# Double_Socket.net
KiCad netlist of a schematic drawn in EAGLE
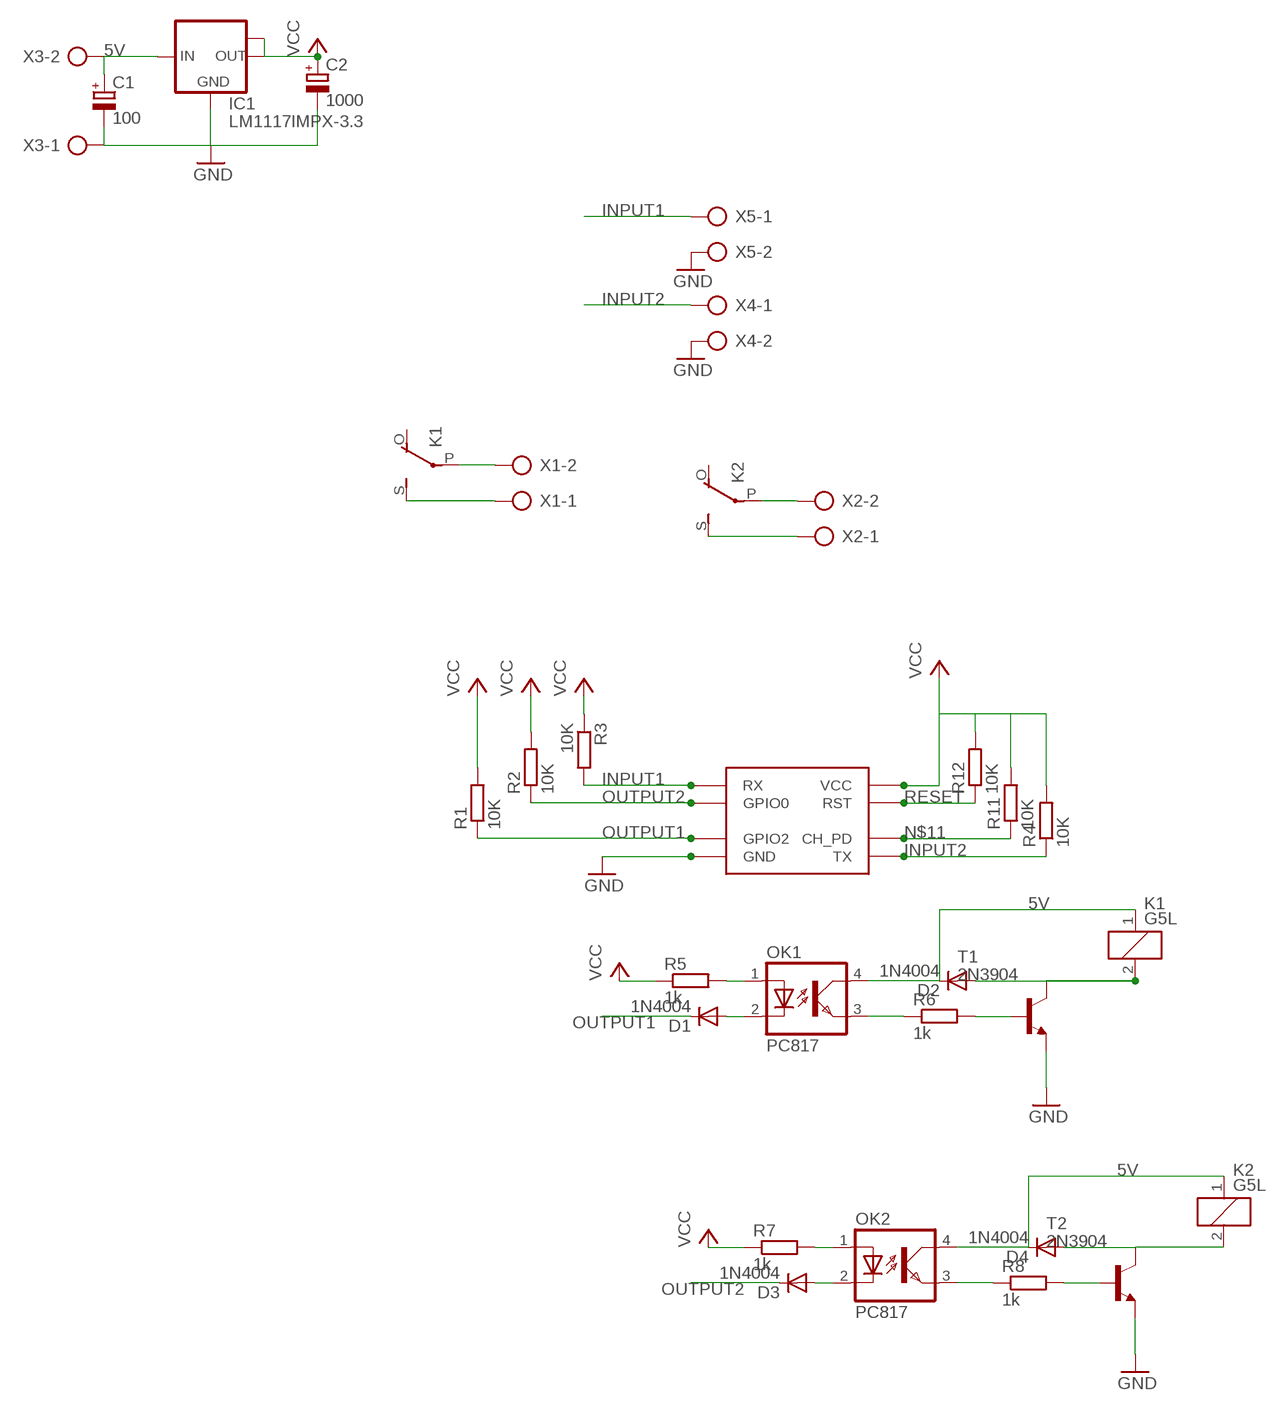
[diagram p0: schematic, sheet 1]

(export (version "E")
  (design (tool "Eeschema 10.0.6"))
  (components
    (comp (ref "C1")
      (value "100")
      (footprint "eagle-import:E5-10,5")
      (libsource (lib "eagle-import") (part "CPOL-EUE5-10.5"))
    )
    (comp (ref "C2")
      (value "1000")
      (footprint "eagle-import:E5-10,5")
      (libsource (lib "eagle-import") (part "CPOL-EUE5-10.5"))
    )
    (comp (ref "D1")
      (value "1N4004")
      (footprint "eagle-import:DO41-10")
      (libsource (lib "eagle-import") (part "1N4004"))
    )
    (comp (ref "D2")
      (value "1N4004")
      (footprint "eagle-import:DO41-10")
      (libsource (lib "eagle-import") (part "1N4004"))
    )
    (comp (ref "D3")
      (value "1N4004")
      (footprint "eagle-import:DO41-10")
      (libsource (lib "eagle-import") (part "1N4004"))
    )
    (comp (ref "D4")
      (value "1N4004")
      (footprint "eagle-import:DO41-10")
      (libsource (lib "eagle-import") (part "1N4004"))
    )
    (comp (ref "IC1")
      (value "LM1117IMPX-3.3")
      (footprint "eagle-import:SOT223")
      (libsource (lib "eagle-import") (part "LM1117IMPX-3.3"))
    )
    (comp (ref "K1")
      (value "G5L")
      (footprint "eagle-import:G5LE")
      (libsource (lib "eagle-import") (part "G5L"))
    )
    (comp (ref "K2")
      (value "G5L")
      (footprint "eagle-import:G5LE")
      (libsource (lib "eagle-import") (part "G5L"))
    )
    (comp (ref "OK1")
      (value "PC817")
      (footprint "eagle-import:DIL04")
      (fields (field (name "MPN") "PC817X4J000F"))
      (libsource (lib "eagle-import") (part "PC817"))
    )
    (comp (ref "OK2")
      (value "PC817")
      (footprint "eagle-import:DIL04")
      (fields (field (name "MPN") "PC817X4J000F"))
      (libsource (lib "eagle-import") (part "PC817"))
    )
    (comp (ref "R1")
      (value "10K")
      (footprint "eagle-import:M0805")
      (libsource (lib "eagle-import") (part "R-EU_M0805"))
    )
    (comp (ref "R2")
      (value "10K")
      (footprint "eagle-import:M0805")
      (libsource (lib "eagle-import") (part "R-EU_M0805"))
    )
    (comp (ref "R3")
      (value "10K")
      (footprint "eagle-import:M0805")
      (libsource (lib "eagle-import") (part "R-EU_M0805"))
    )
    (comp (ref "R4")
      (value "10K")
      (footprint "eagle-import:M0805")
      (libsource (lib "eagle-import") (part "R-EU_M0805"))
    )
    (comp (ref "R5")
      (value "1k")
      (footprint "eagle-import:M0805")
      (libsource (lib "eagle-import") (part "R-EU_M0805"))
    )
    (comp (ref "R6")
      (value "1k")
      (footprint "eagle-import:M0805")
      (libsource (lib "eagle-import") (part "R-EU_M0805"))
    )
    (comp (ref "R7")
      (value "1k")
      (footprint "eagle-import:M0805")
      (libsource (lib "eagle-import") (part "R-EU_M0805"))
    )
    (comp (ref "R8")
      (value "1k")
      (footprint "eagle-import:M0805")
      (libsource (lib "eagle-import") (part "R-EU_M0805"))
    )
    (comp (ref "R11")
      (value "10K")
      (footprint "eagle-import:M0805")
      (libsource (lib "eagle-import") (part "R-EU_M0805"))
    )
    (comp (ref "R12")
      (value "10K")
      (footprint "eagle-import:M0805")
      (libsource (lib "eagle-import") (part "R-EU_M0805"))
    )
    (comp (ref "T1")
      (value "2N3904")
      (footprint "eagle-import:TO92")
      (libsource (lib "eagle-import") (part "2N3904"))
    )
    (comp (ref "T2")
      (value "2N3904")
      (footprint "eagle-import:TO92")
      (libsource (lib "eagle-import") (part "2N3904"))
    )
    (comp (ref "U$2")
      (value "ESP8266")
      (footprint "eagle-import:ESP8266")
      (libsource (lib "eagle-import") (part "ESP8266"))
    )
    (comp (ref "X1")
      (value "AK500/2-H")
      (footprint "eagle-import:AK500_2-H")
      (libsource (lib "eagle-import") (part "AK500/2-H"))
    )
    (comp (ref "X2")
      (value "AK500/2-H")
      (footprint "eagle-import:AK500_2-H")
      (libsource (lib "eagle-import") (part "AK500/2-H"))
    )
    (comp (ref "X3")
      (value "AK500/2-H")
      (footprint "eagle-import:AK500_2-H")
      (libsource (lib "eagle-import") (part "AK500/2-H"))
    )
    (comp (ref "X4")
      (value "AK500/2-H")
      (footprint "eagle-import:AK500_2-H")
      (libsource (lib "eagle-import") (part "AK500/2-H"))
    )
    (comp (ref "X5")
      (value "AK500/2-H")
      (footprint "eagle-import:AK500_2-H")
      (libsource (lib "eagle-import") (part "AK500/2-H"))
    )
  )
  (nets
    (net (code "1") (name "/5V") (class "Default")
      (node (ref "C1") (pin "+") (pinfunction "+_+") (pintype "passive"))
      (node (ref "D2") (pin "C") (pinfunction "C_C") (pintype "passive"))
      (node (ref "D4") (pin "C") (pinfunction "C_C") (pintype "passive"))
      (node (ref "IC1") (pin "3") (pinfunction "IN_3") (pintype "input"))
      (node (ref "K1") (pin "1") (pinfunction "1_1") (pintype "passive"))
      (node (ref "K2") (pin "1") (pinfunction "1_1") (pintype "passive"))
      (node (ref "OK1") (pin "4") (pinfunction "COL_4") (pintype "passive"))
      (node (ref "OK2") (pin "4") (pinfunction "COL_4") (pintype "passive"))
      (node (ref "X3") (pin "2") (pinfunction "KL_2") (pintype "passive"))
    )
    (net (code "2") (name "/INPUT1") (class "Default")
      (node (ref "R3") (pin "2") (pinfunction "2_2") (pintype "passive"))
      (node (ref "U$2") (pin "RX") (pinfunction "RX_RX") (pintype "bidirectional"))
      (node (ref "X5") (pin "1") (pinfunction "KL_1") (pintype "passive"))
    )
    (net (code "3") (name "/INPUT2") (class "Default")
      (node (ref "R4") (pin "1") (pinfunction "1_1") (pintype "passive"))
      (node (ref "U$2") (pin "TX") (pinfunction "TX_TX") (pintype "bidirectional"))
      (node (ref "X4") (pin "1") (pinfunction "KL_1") (pintype "passive"))
    )
    (net (code "4") (name "/N$11") (class "Default")
      (node (ref "R11") (pin "1") (pinfunction "1_1") (pintype "passive"))
      (node (ref "U$2") (pin "CH_PD") (pinfunction "CH_PD_CH_PD") (pintype "bidirectional"))
    )
    (net (code "5") (name "/OUTPUT1") (class "Default")
      (node (ref "D1") (pin "C") (pinfunction "C_C") (pintype "passive"))
      (node (ref "R1") (pin "1") (pinfunction "1_1") (pintype "passive"))
      (node (ref "U$2") (pin "GPIO2") (pinfunction "GPIO2_GPIO2") (pintype "bidirectional"))
    )
    (net (code "6") (name "/OUTPUT2") (class "Default")
      (node (ref "D3") (pin "C") (pinfunction "C_C") (pintype "passive"))
      (node (ref "R2") (pin "1") (pinfunction "1_1") (pintype "passive"))
      (node (ref "U$2") (pin "GPIO0") (pinfunction "GPIO0_GPIO0") (pintype "bidirectional"))
    )
    (net (code "7") (name "/RESET") (class "Default")
      (node (ref "R12") (pin "1") (pinfunction "1_1") (pintype "passive"))
      (node (ref "U$2") (pin "RST") (pinfunction "RST_RST") (pintype "bidirectional"))
    )
    (net (code "8") (name "GND") (class "Default")
      (node (ref "C1") (pin "-") (pinfunction "-_-") (pintype "passive"))
      (node (ref "C2") (pin "-") (pinfunction "-_-") (pintype "passive"))
      (node (ref "IC1") (pin "1") (pinfunction "GND_1") (pintype "input"))
      (node (ref "T1") (pin "3") (pinfunction "E_3") (pintype "passive"))
      (node (ref "T2") (pin "3") (pinfunction "E_3") (pintype "passive"))
      (node (ref "U$2") (pin "GND") (pinfunction "GND_GND") (pintype "bidirectional"))
      (node (ref "X3") (pin "1") (pinfunction "KL_1") (pintype "passive"))
      (node (ref "X4") (pin "2") (pinfunction "KL_2") (pintype "passive"))
      (node (ref "X5") (pin "2") (pinfunction "KL_2") (pintype "passive"))
    )
    (net (code "9") (name "Net-(OK1-A)") (class "Default")
      (node (ref "OK1") (pin "1") (pinfunction "A_1") (pintype "passive"))
      (node (ref "R5") (pin "2") (pinfunction "2_2") (pintype "passive"))
    )
    (net (code "10") (name "Net-(OK1-C)") (class "Default")
      (node (ref "D1") (pin "A") (pinfunction "A_A") (pintype "passive"))
      (node (ref "OK1") (pin "2") (pinfunction "C_2") (pintype "passive"))
    )
    (net (code "11") (name "Net-(OK1-EMIT)") (class "Default")
      (node (ref "OK1") (pin "3") (pinfunction "EMIT_3") (pintype "passive"))
      (node (ref "R6") (pin "1") (pinfunction "1_1") (pintype "passive"))
    )
    (net (code "12") (name "Net-(OK2-A)") (class "Default")
      (node (ref "OK2") (pin "1") (pinfunction "A_1") (pintype "passive"))
      (node (ref "R7") (pin "2") (pinfunction "2_2") (pintype "passive"))
    )
    (net (code "13") (name "Net-(OK2-C)") (class "Default")
      (node (ref "D3") (pin "A") (pinfunction "A_A") (pintype "passive"))
      (node (ref "OK2") (pin "2") (pinfunction "C_2") (pintype "passive"))
    )
    (net (code "14") (name "Net-(OK2-EMIT)") (class "Default")
      (node (ref "OK2") (pin "3") (pinfunction "EMIT_3") (pintype "passive"))
      (node (ref "R8") (pin "1") (pinfunction "1_1") (pintype "passive"))
    )
    (net (code "15") (name "Net-(T1-B)") (class "Default")
      (node (ref "R6") (pin "2") (pinfunction "2_2") (pintype "passive"))
      (node (ref "T1") (pin "2") (pinfunction "B_2") (pintype "passive"))
    )
    (net (code "16") (name "Net-(T1-C)") (class "Default")
      (node (ref "D2") (pin "A") (pinfunction "A_A") (pintype "passive"))
      (node (ref "K1") (pin "2") (pinfunction "2_2") (pintype "passive"))
      (node (ref "T1") (pin "1") (pinfunction "C_1") (pintype "passive"))
    )
    (net (code "17") (name "Net-(T2-B)") (class "Default")
      (node (ref "R8") (pin "2") (pinfunction "2_2") (pintype "passive"))
      (node (ref "T2") (pin "2") (pinfunction "B_2") (pintype "passive"))
    )
    (net (code "18") (name "Net-(T2-C)") (class "Default")
      (node (ref "D4") (pin "A") (pinfunction "A_A") (pintype "passive"))
      (node (ref "K2") (pin "2") (pinfunction "2_2") (pintype "passive"))
      (node (ref "T2") (pin "1") (pinfunction "C_1") (pintype "passive"))
    )
    (net (code "19") (name "Net-(X1A-KL)") (class "Default")
      (node (ref "K1") (pin "S") (pinfunction "S_S") (pintype "passive"))
      (node (ref "X1") (pin "1") (pinfunction "KL_1") (pintype "passive"))
    )
    (net (code "20") (name "Net-(X1B-KL)") (class "Default")
      (node (ref "K1") (pin "P") (pinfunction "P_P") (pintype "passive"))
      (node (ref "X1") (pin "2") (pinfunction "KL_2") (pintype "passive"))
    )
    (net (code "21") (name "Net-(X2A-KL)") (class "Default")
      (node (ref "K2") (pin "S") (pinfunction "S_S") (pintype "passive"))
      (node (ref "X2") (pin "1") (pinfunction "KL_1") (pintype "passive"))
    )
    (net (code "22") (name "Net-(X2B-KL)") (class "Default")
      (node (ref "K2") (pin "P") (pinfunction "P_P") (pintype "passive"))
      (node (ref "X2") (pin "2") (pinfunction "KL_2") (pintype "passive"))
    )
    (net (code "23") (name "VCC") (class "Default")
      (node (ref "C2") (pin "+") (pinfunction "+_+") (pintype "passive"))
      (node (ref "IC1") (pin "2") (pinfunction "OUT_2") (pintype "passive"))
      (node (ref "IC1") (pin "TAB") (pinfunction "OUT1_TAB") (pintype "passive"))
      (node (ref "R1") (pin "2") (pinfunction "2_2") (pintype "passive"))
      (node (ref "R11") (pin "2") (pinfunction "2_2") (pintype "passive"))
      (node (ref "R12") (pin "2") (pinfunction "2_2") (pintype "passive"))
      (node (ref "R2") (pin "2") (pinfunction "2_2") (pintype "passive"))
      (node (ref "R3") (pin "1") (pinfunction "1_1") (pintype "passive"))
      (node (ref "R4") (pin "2") (pinfunction "2_2") (pintype "passive"))
      (node (ref "R5") (pin "1") (pinfunction "1_1") (pintype "passive"))
      (node (ref "R7") (pin "1") (pinfunction "1_1") (pintype "passive"))
      (node (ref "U$2") (pin "VCC") (pinfunction "VCC_VCC") (pintype "bidirectional"))
    )
    (net (code "24") (name "unconnected-(K1-PadO)") (class "Default")
      (node (ref "K1") (pin "O") (pinfunction "O_O") (pintype "passive"))
    )
    (net (code "25") (name "unconnected-(K2-PadO)") (class "Default")
      (node (ref "K2") (pin "O") (pinfunction "O_O") (pintype "passive"))
    )
  )
)
